# SCH_ESPHome-Aldes-T_One-V2.net
KiCad netlist of a schematic drawn in EasyEDA
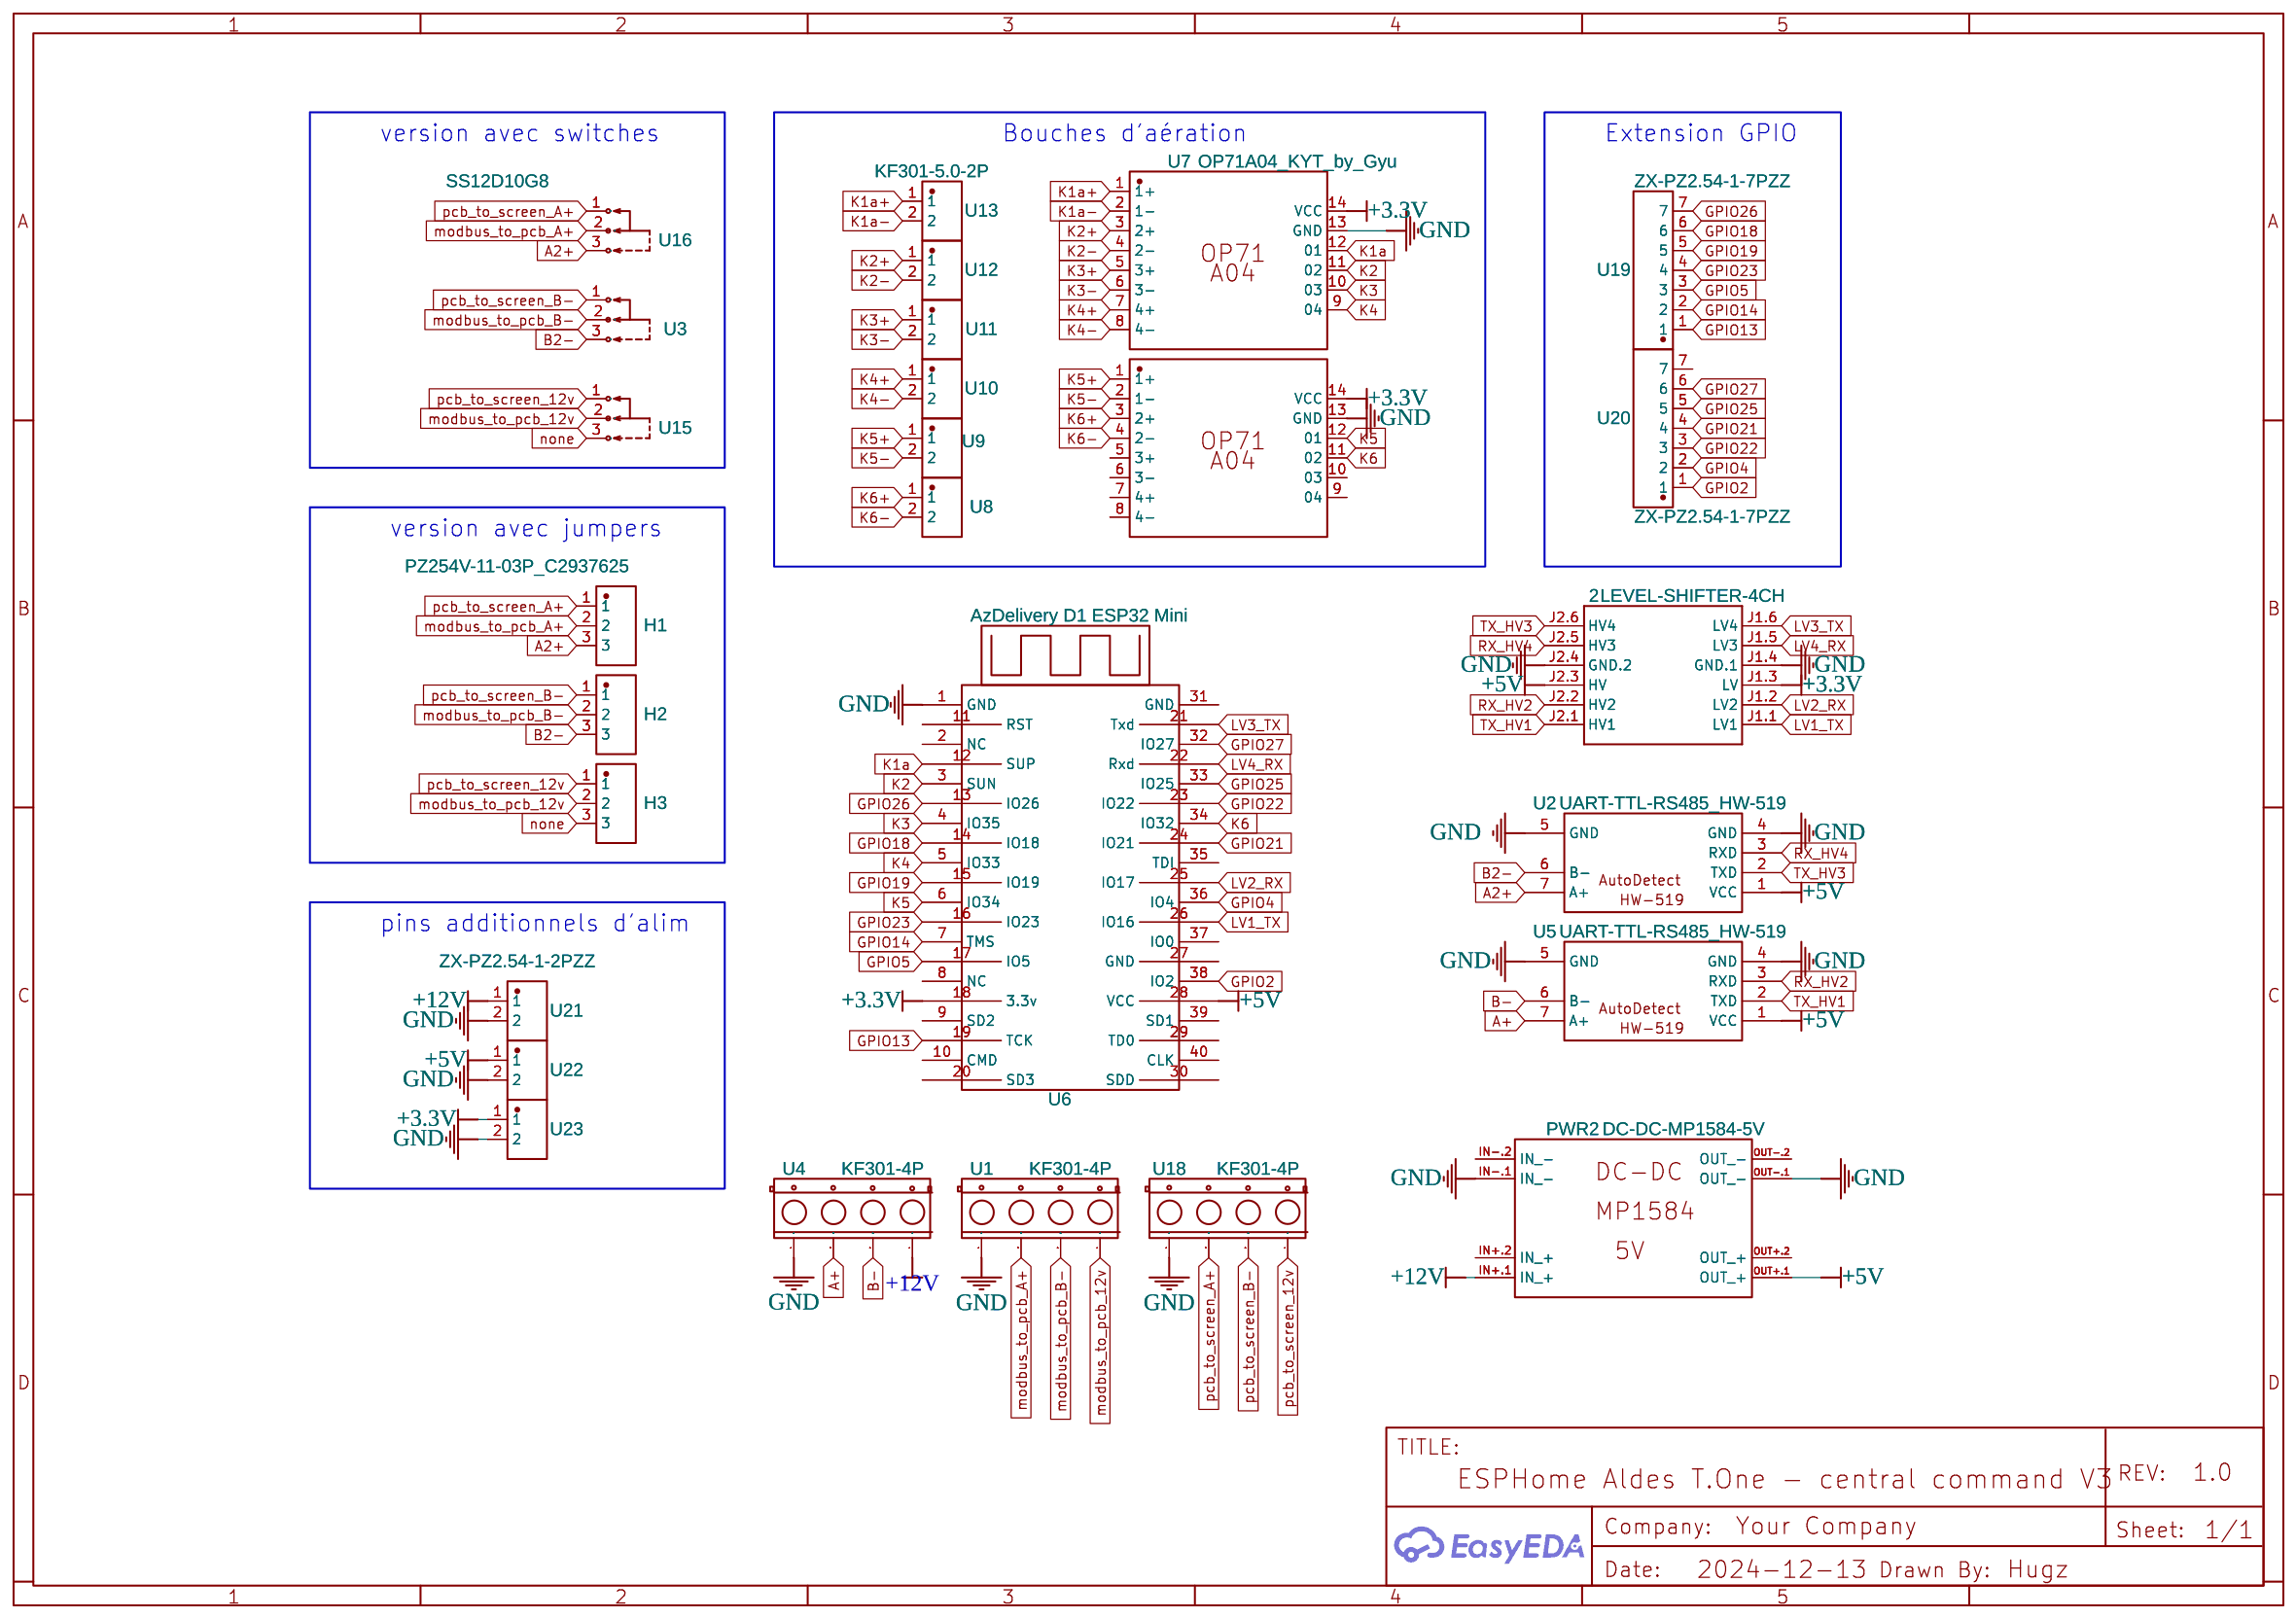
[diagram p0: schematic sheet]

(export (version "E")
  (design (tool "Eeschema 10.0.6"))
  (components
    (comp (ref "2") (value "LEVEL-SHIFTER-4CH") (libsource (lib "") (part "LEVEL-SHIFTER-4CH")))
    (comp (ref "H1")
      (value "PZ254V-11-03P_C2937625")
      (fields (field (name "Manufacturer Part") "PZ254V-11-03P") (field (name "Manufacturer") "XFCN(兴飞)"))
      (libsource (lib "") (part "PZ254V-11-03P_C2937625"))
    )
    (comp (ref "H2")
      (value "PZ254V-11-03P_C2937625")
      (fields (field (name "Manufacturer Part") "PZ254V-11-03P") (field (name "Manufacturer") "XFCN(兴飞)"))
      (libsource (lib "") (part "PZ254V-11-03P_C2937625"))
    )
    (comp (ref "H3")
      (value "PZ254V-11-03P_C2937625")
      (fields (field (name "Manufacturer Part") "PZ254V-11-03P") (field (name "Manufacturer") "XFCN(兴飞)"))
      (libsource (lib "") (part "PZ254V-11-03P_C2937625"))
    )
    (comp (ref "PWR2") (value "DC-DC-MP1584-5V") (libsource (lib "") (part "DC-DC-MP1584-5V")))
    (comp (ref "U1")
      (value "KF301-4P")
      (fields (field (name "Manufacturer Part") "KF301"))
      (libsource (lib "") (part "KF301-4P"))
    )
    (comp (ref "U2") (value "UART-TTL-RS485_HW-519") (libsource (lib "") (part "UART-TTL-RS485_HW-519")))
    (comp (ref "U3") (value "SS12D10G8") (libsource (lib "") (part "SS12D10G8")))
    (comp (ref "U4")
      (value "KF301-4P")
      (fields (field (name "Manufacturer Part") "KF301"))
      (libsource (lib "") (part "KF301-4P"))
    )
    (comp (ref "U5") (value "UART-TTL-RS485_HW-519") (libsource (lib "") (part "UART-TTL-RS485_HW-519")))
    (comp (ref "U6")
      (value "AzDelivery D1 ESP32 Mini")
      (fields (field (name "Manufacturer Part") "D1 Mini ESP32") (field (name "Manufacturer") "AzDelivery"))
      (libsource (lib "") (part "AzDelivery D1 ESP32 Mini"))
    )
    (comp (ref "U7") (value "OP71A04_KYT_by_Gyu") (libsource (lib "") (part "OP71A04_KYT_by_Gyu")))
    (comp (ref "U8")
      (value "KF301-5.0-2P")
      (fields (field (name "Manufacturer") "KEFA(科发)"))
      (libsource (lib "") (part "KF301-5.0-2P"))
    )
    (comp (ref "U9")
      (value "KF301-5.0-2P")
      (fields (field (name "Manufacturer") "KEFA(科发)"))
      (libsource (lib "") (part "KF301-5.0-2P"))
    )
    (comp (ref "U10")
      (value "KF301-5.0-2P")
      (fields (field (name "Manufacturer") "KEFA(科发)"))
      (libsource (lib "") (part "KF301-5.0-2P"))
    )
    (comp (ref "U11")
      (value "KF301-5.0-2P")
      (fields (field (name "Manufacturer") "KEFA(科发)"))
      (libsource (lib "") (part "KF301-5.0-2P"))
    )
    (comp (ref "U12")
      (value "KF301-5.0-2P")
      (fields (field (name "Manufacturer") "KEFA(科发)"))
      (libsource (lib "") (part "KF301-5.0-2P"))
    )
    (comp (ref "U13")
      (value "KF301-5.0-2P")
      (fields (field (name "Manufacturer") "KEFA(科发)"))
      (libsource (lib "") (part "KF301-5.0-2P"))
    )
    (comp (ref "U14") (value "OP71A04_KYT_by_Gyu") (libsource (lib "") (part "OP71A04_KYT_by_Gyu")))
    (comp (ref "U15") (value "SS12D10G8") (libsource (lib "") (part "SS12D10G8")))
    (comp (ref "U16") (value "SS12D10G8") (libsource (lib "") (part "SS12D10G8")))
    (comp (ref "U18")
      (value "KF301-4P")
      (fields (field (name "Manufacturer Part") "KF301"))
      (libsource (lib "") (part "KF301-4P"))
    )
    (comp (ref "U19")
      (value "ZX-PZ2.54-1-7PZZ")
      (fields (field (name "Manufacturer") "Megastar(兆星)"))
      (libsource (lib "") (part "ZX-PZ2.54-1-7PZZ"))
    )
    (comp (ref "U20")
      (value "ZX-PZ2.54-1-7PZZ")
      (fields (field (name "Manufacturer") "Megastar(兆星)"))
      (libsource (lib "") (part "ZX-PZ2.54-1-7PZZ"))
    )
    (comp (ref "U21")
      (value "ZX-PZ2.54-1-2PZZ")
      (fields (field (name "Manufacturer") "Megastar(兆星)"))
      (libsource (lib "") (part "ZX-PZ2.54-1-2PZZ"))
    )
    (comp (ref "U22")
      (value "ZX-PZ2.54-1-2PZZ")
      (fields (field (name "Manufacturer") "Megastar(兆星)"))
      (libsource (lib "") (part "ZX-PZ2.54-1-2PZZ"))
    )
    (comp (ref "U23")
      (value "ZX-PZ2.54-1-2PZZ")
      (fields (field (name "Manufacturer") "Megastar(兆星)"))
      (libsource (lib "") (part "ZX-PZ2.54-1-2PZZ"))
    )
  )
  (nets
    (net (code "1") (name "+3.3V") (class "Default")
      (node (ref "2") (pin "J1.3") (pinfunction "LV_J1.3") (pintype "bidirectional"))
      (node (ref "U14") (pin "14") (pinfunction "VCC_14") (pintype "unspecified"))
      (node (ref "U23") (pin "1") (pinfunction "1_1") (pintype "unspecified"))
      (node (ref "U6") (pin "18") (pinfunction "3.3v_18") (pintype "unspecified"))
      (node (ref "U7") (pin "14") (pinfunction "VCC_14") (pintype "unspecified"))
    )
    (net (code "2") (name "+5V") (class "Default")
      (node (ref "2") (pin "J2.3") (pinfunction "HV_J2.3") (pintype "bidirectional"))
      (node (ref "PWR2") (pin "OUT+.1") (pinfunction "OUT_+_OUT+.1") (pintype "unspecified"))
      (node (ref "U2") (pin "1") (pinfunction "VCC_1") (pintype "unspecified"))
      (node (ref "U22") (pin "1") (pinfunction "1_1") (pintype "unspecified"))
      (node (ref "U5") (pin "1") (pinfunction "VCC_1") (pintype "unspecified"))
      (node (ref "U6") (pin "28") (pinfunction "VCC_28") (pintype "unspecified"))
    )
    (net (code "3") (name "+12V") (class "Default")
      (node (ref "PWR2") (pin "IN+.1") (pinfunction "IN_+_IN+.1") (pintype "unspecified"))
      (node (ref "U21") (pin "1") (pinfunction "1_1") (pintype "unspecified"))
      (node (ref "U4") (pin "4") (pinfunction "4_4") (pintype "unspecified"))
    )
    (net (code "4") (name "A+") (class "Default")
      (node (ref "U4") (pin "2") (pinfunction "2_2") (pintype "unspecified"))
      (node (ref "U5") (pin "7") (pinfunction "A+_7") (pintype "unspecified"))
    )
    (net (code "5") (name "A2+") (class "Default")
      (node (ref "H1") (pin "3") (pinfunction "3_3") (pintype "unspecified"))
      (node (ref "U16") (pin "3") (pinfunction "3_3") (pintype "unspecified"))
      (node (ref "U2") (pin "7") (pinfunction "A+_7") (pintype "unspecified"))
    )
    (net (code "6") (name "B-") (class "Default")
      (node (ref "U4") (pin "3") (pinfunction "3_3") (pintype "unspecified"))
      (node (ref "U5") (pin "6") (pinfunction "B-_6") (pintype "unspecified"))
    )
    (net (code "7") (name "B2-") (class "Default")
      (node (ref "H2") (pin "3") (pinfunction "3_3") (pintype "unspecified"))
      (node (ref "U2") (pin "6") (pinfunction "B-_6") (pintype "unspecified"))
      (node (ref "U3") (pin "3") (pinfunction "3_3") (pintype "unspecified"))
    )
    (net (code "8") (name "GND") (class "Default")
      (node (ref "2") (pin "J1.4") (pinfunction "GND.1_J1.4") (pintype "bidirectional"))
      (node (ref "2") (pin "J2.4") (pinfunction "GND.2_J2.4") (pintype "bidirectional"))
      (node (ref "PWR2") (pin "IN-.1") (pinfunction "IN_-_IN-.1") (pintype "unspecified"))
      (node (ref "PWR2") (pin "OUT-.1") (pinfunction "OUT_-_OUT-.1") (pintype "unspecified"))
      (node (ref "U1") (pin "1") (pinfunction "1_1") (pintype "unspecified"))
      (node (ref "U14") (pin "13") (pinfunction "GND_13") (pintype "unspecified"))
      (node (ref "U18") (pin "1") (pinfunction "1_1") (pintype "unspecified"))
      (node (ref "U2") (pin "4") (pinfunction "GND_4") (pintype "unspecified"))
      (node (ref "U2") (pin "5") (pinfunction "GND_5") (pintype "unspecified"))
      (node (ref "U21") (pin "2") (pinfunction "2_2") (pintype "unspecified"))
      (node (ref "U22") (pin "2") (pinfunction "2_2") (pintype "unspecified"))
      (node (ref "U23") (pin "2") (pinfunction "2_2") (pintype "unspecified"))
      (node (ref "U4") (pin "1") (pinfunction "1_1") (pintype "unspecified"))
      (node (ref "U5") (pin "4") (pinfunction "GND_4") (pintype "unspecified"))
      (node (ref "U5") (pin "5") (pinfunction "GND_5") (pintype "unspecified"))
      (node (ref "U6") (pin "1") (pinfunction "GND_1") (pintype "unspecified"))
      (node (ref "U7") (pin "13") (pinfunction "GND_13") (pintype "unspecified"))
    )
    (net (code "9") (name "GPIO2") (class "Default")
      (node (ref "U20") (pin "1") (pinfunction "1_1") (pintype "unspecified"))
      (node (ref "U6") (pin "38") (pinfunction "IO2_38") (pintype "unspecified"))
    )
    (net (code "10") (name "GPIO4") (class "Default")
      (node (ref "U20") (pin "2") (pinfunction "2_2") (pintype "unspecified"))
      (node (ref "U6") (pin "36") (pinfunction "IO4_36") (pintype "unspecified"))
    )
    (net (code "11") (name "GPIO5") (class "Default")
      (node (ref "U19") (pin "3") (pinfunction "3_3") (pintype "unspecified"))
      (node (ref "U6") (pin "17") (pinfunction "IO5_17") (pintype "unspecified"))
    )
    (net (code "12") (name "GPIO13") (class "Default")
      (node (ref "U19") (pin "1") (pinfunction "1_1") (pintype "unspecified"))
      (node (ref "U6") (pin "19") (pinfunction "TCK_19") (pintype "unspecified"))
    )
    (net (code "13") (name "GPIO14") (class "Default")
      (node (ref "U19") (pin "2") (pinfunction "2_2") (pintype "unspecified"))
      (node (ref "U6") (pin "7") (pinfunction "TMS_7") (pintype "unspecified"))
    )
    (net (code "14") (name "GPIO18") (class "Default")
      (node (ref "U19") (pin "6") (pinfunction "6_6") (pintype "unspecified"))
      (node (ref "U6") (pin "14") (pinfunction "IO18_14") (pintype "unspecified"))
    )
    (net (code "15") (name "GPIO19") (class "Default")
      (node (ref "U19") (pin "5") (pinfunction "5_5") (pintype "unspecified"))
      (node (ref "U6") (pin "15") (pinfunction "IO19_15") (pintype "unspecified"))
    )
    (net (code "16") (name "GPIO21") (class "Default")
      (node (ref "U20") (pin "4") (pinfunction "4_4") (pintype "unspecified"))
      (node (ref "U6") (pin "24") (pinfunction "IO21_24") (pintype "unspecified"))
    )
    (net (code "17") (name "GPIO22") (class "Default")
      (node (ref "U20") (pin "3") (pinfunction "3_3") (pintype "unspecified"))
      (node (ref "U6") (pin "23") (pinfunction "IO22_23") (pintype "unspecified"))
    )
    (net (code "18") (name "GPIO23") (class "Default")
      (node (ref "U19") (pin "4") (pinfunction "4_4") (pintype "unspecified"))
      (node (ref "U6") (pin "16") (pinfunction "IO23_16") (pintype "unspecified"))
    )
    (net (code "19") (name "GPIO25") (class "Default")
      (node (ref "U20") (pin "5") (pinfunction "5_5") (pintype "unspecified"))
      (node (ref "U6") (pin "33") (pinfunction "IO25_33") (pintype "unspecified"))
    )
    (net (code "20") (name "GPIO26") (class "Default")
      (node (ref "U19") (pin "7") (pinfunction "7_7") (pintype "unspecified"))
      (node (ref "U6") (pin "13") (pinfunction "IO26_13") (pintype "unspecified"))
    )
    (net (code "21") (name "GPIO27") (class "Default")
      (node (ref "U20") (pin "6") (pinfunction "6_6") (pintype "unspecified"))
      (node (ref "U6") (pin "32") (pinfunction "IO27_32") (pintype "unspecified"))
    )
    (net (code "22") (name "K1a") (class "Default")
      (node (ref "U6") (pin "12") (pinfunction "SUP_12") (pintype "unspecified"))
      (node (ref "U7") (pin "12") (pinfunction "01_12") (pintype "unspecified"))
    )
    (net (code "23") (name "K1a+") (class "Default")
      (node (ref "U13") (pin "1") (pinfunction "1_1") (pintype "unspecified"))
      (node (ref "U7") (pin "1") (pinfunction "1+_1") (pintype "unspecified"))
    )
    (net (code "24") (name "K1a-") (class "Default")
      (node (ref "U13") (pin "2") (pinfunction "2_2") (pintype "unspecified"))
      (node (ref "U7") (pin "2") (pinfunction "1-_2") (pintype "unspecified"))
    )
    (net (code "25") (name "K2") (class "Default")
      (node (ref "U6") (pin "3") (pinfunction "SUN_3") (pintype "unspecified"))
      (node (ref "U7") (pin "11") (pinfunction "02_11") (pintype "unspecified"))
    )
    (net (code "26") (name "K2+") (class "Default")
      (node (ref "U12") (pin "1") (pinfunction "1_1") (pintype "unspecified"))
      (node (ref "U7") (pin "3") (pinfunction "2+_3") (pintype "unspecified"))
    )
    (net (code "27") (name "K2-") (class "Default")
      (node (ref "U12") (pin "2") (pinfunction "2_2") (pintype "unspecified"))
      (node (ref "U7") (pin "4") (pinfunction "2-_4") (pintype "unspecified"))
    )
    (net (code "28") (name "K3") (class "Default")
      (node (ref "U6") (pin "4") (pinfunction "IO35_4") (pintype "unspecified"))
      (node (ref "U7") (pin "10") (pinfunction "03_10") (pintype "unspecified"))
    )
    (net (code "29") (name "K3+") (class "Default")
      (node (ref "U11") (pin "1") (pinfunction "1_1") (pintype "unspecified"))
      (node (ref "U7") (pin "5") (pinfunction "3+_5") (pintype "unspecified"))
    )
    (net (code "30") (name "K3-") (class "Default")
      (node (ref "U11") (pin "2") (pinfunction "2_2") (pintype "unspecified"))
      (node (ref "U7") (pin "6") (pinfunction "3-_6") (pintype "unspecified"))
    )
    (net (code "31") (name "K4") (class "Default")
      (node (ref "U6") (pin "5") (pinfunction "IO33_5") (pintype "unspecified"))
      (node (ref "U7") (pin "9") (pinfunction "04_9") (pintype "unspecified"))
    )
    (net (code "32") (name "K4+") (class "Default")
      (node (ref "U10") (pin "1") (pinfunction "1_1") (pintype "unspecified"))
      (node (ref "U7") (pin "7") (pinfunction "4+_7") (pintype "unspecified"))
    )
    (net (code "33") (name "K4-") (class "Default")
      (node (ref "U10") (pin "2") (pinfunction "2_2") (pintype "unspecified"))
      (node (ref "U7") (pin "8") (pinfunction "4-_8") (pintype "unspecified"))
    )
    (net (code "34") (name "K5") (class "Default")
      (node (ref "U14") (pin "12") (pinfunction "01_12") (pintype "unspecified"))
      (node (ref "U6") (pin "6") (pinfunction "IO34_6") (pintype "unspecified"))
    )
    (net (code "35") (name "K5+") (class "Default")
      (node (ref "U14") (pin "1") (pinfunction "1+_1") (pintype "unspecified"))
      (node (ref "U9") (pin "1") (pinfunction "1_1") (pintype "unspecified"))
    )
    (net (code "36") (name "K5-") (class "Default")
      (node (ref "U14") (pin "2") (pinfunction "1-_2") (pintype "unspecified"))
      (node (ref "U9") (pin "2") (pinfunction "2_2") (pintype "unspecified"))
    )
    (net (code "37") (name "K6") (class "Default")
      (node (ref "U14") (pin "11") (pinfunction "02_11") (pintype "unspecified"))
      (node (ref "U6") (pin "34") (pinfunction "IO32_34") (pintype "unspecified"))
    )
    (net (code "38") (name "K6+") (class "Default")
      (node (ref "U14") (pin "3") (pinfunction "2+_3") (pintype "unspecified"))
      (node (ref "U8") (pin "1") (pinfunction "1_1") (pintype "unspecified"))
    )
    (net (code "39") (name "K6-") (class "Default")
      (node (ref "U14") (pin "4") (pinfunction "2-_4") (pintype "unspecified"))
      (node (ref "U8") (pin "2") (pinfunction "2_2") (pintype "unspecified"))
    )
    (net (code "40") (name "LV1_TX") (class "Default")
      (node (ref "2") (pin "J1.1") (pinfunction "LV1_J1.1") (pintype "bidirectional"))
      (node (ref "U6") (pin "26") (pinfunction "IO16_26") (pintype "unspecified"))
    )
    (net (code "41") (name "LV2_RX") (class "Default")
      (node (ref "2") (pin "J1.2") (pinfunction "LV2_J1.2") (pintype "bidirectional"))
      (node (ref "U6") (pin "25") (pinfunction "IO17_25") (pintype "unspecified"))
    )
    (net (code "42") (name "LV3_TX") (class "Default")
      (node (ref "2") (pin "J1.6") (pinfunction "LV4_J1.6") (pintype "bidirectional"))
      (node (ref "U6") (pin "21") (pinfunction "Txd_21") (pintype "unspecified"))
    )
    (net (code "43") (name "LV4_RX") (class "Default")
      (node (ref "2") (pin "J1.5") (pinfunction "LV3_J1.5") (pintype "bidirectional"))
      (node (ref "U6") (pin "22") (pinfunction "Rxd_22") (pintype "unspecified"))
    )
    (net (code "44") (name "RX_HV2") (class "Default")
      (node (ref "2") (pin "J2.2") (pinfunction "HV2_J2.2") (pintype "bidirectional"))
      (node (ref "U5") (pin "3") (pinfunction "RXD_3") (pintype "unspecified"))
    )
    (net (code "45") (name "RX_HV4") (class "Default")
      (node (ref "2") (pin "J2.5") (pinfunction "HV3_J2.5") (pintype "bidirectional"))
      (node (ref "U2") (pin "3") (pinfunction "RXD_3") (pintype "unspecified"))
    )
    (net (code "46") (name "TX_HV1") (class "Default")
      (node (ref "2") (pin "J2.1") (pinfunction "HV1_J2.1") (pintype "bidirectional"))
      (node (ref "U5") (pin "2") (pinfunction "TXD_2") (pintype "unspecified"))
    )
    (net (code "47") (name "TX_HV3") (class "Default")
      (node (ref "2") (pin "J2.6") (pinfunction "HV4_J2.6") (pintype "bidirectional"))
      (node (ref "U2") (pin "2") (pinfunction "TXD_2") (pintype "unspecified"))
    )
    (net (code "48") (name "modbus_to_pcb_12v") (class "Default")
      (node (ref "H3") (pin "2") (pinfunction "2_2") (pintype "unspecified"))
      (node (ref "U1") (pin "4") (pinfunction "4_4") (pintype "unspecified"))
      (node (ref "U15") (pin "2") (pinfunction "2_2") (pintype "unspecified"))
    )
    (net (code "49") (name "modbus_to_pcb_A+") (class "Default")
      (node (ref "H1") (pin "2") (pinfunction "2_2") (pintype "unspecified"))
      (node (ref "U1") (pin "2") (pinfunction "2_2") (pintype "unspecified"))
      (node (ref "U16") (pin "2") (pinfunction "2_2") (pintype "unspecified"))
    )
    (net (code "50") (name "modbus_to_pcb_B-") (class "Default")
      (node (ref "H2") (pin "2") (pinfunction "2_2") (pintype "unspecified"))
      (node (ref "U1") (pin "3") (pinfunction "3_3") (pintype "unspecified"))
      (node (ref "U3") (pin "2") (pinfunction "2_2") (pintype "unspecified"))
    )
    (net (code "51") (name "none") (class "Default")
      (node (ref "H3") (pin "3") (pinfunction "3_3") (pintype "unspecified"))
      (node (ref "U15") (pin "3") (pinfunction "3_3") (pintype "unspecified"))
    )
    (net (code "52") (name "pcb_to_screen_12v") (class "Default")
      (node (ref "H3") (pin "1") (pinfunction "1_1") (pintype "unspecified"))
      (node (ref "U15") (pin "1") (pinfunction "1_1") (pintype "unspecified"))
      (node (ref "U18") (pin "4") (pinfunction "4_4") (pintype "unspecified"))
    )
    (net (code "53") (name "pcb_to_screen_A+") (class "Default")
      (node (ref "H1") (pin "1") (pinfunction "1_1") (pintype "unspecified"))
      (node (ref "U16") (pin "1") (pinfunction "1_1") (pintype "unspecified"))
      (node (ref "U18") (pin "2") (pinfunction "2_2") (pintype "unspecified"))
    )
    (net (code "54") (name "pcb_to_screen_B-") (class "Default")
      (node (ref "H2") (pin "1") (pinfunction "1_1") (pintype "unspecified"))
      (node (ref "U18") (pin "3") (pinfunction "3_3") (pintype "unspecified"))
      (node (ref "U3") (pin "1") (pinfunction "1_1") (pintype "unspecified"))
    )
    (net (code "55") (name "unconnected-(PWR2-IN_+-PadIN+.2)") (class "Default")
      (node (ref "PWR2") (pin "IN+.2") (pinfunction "IN_+_IN+.2") (pintype "unspecified"))
    )
    (net (code "56") (name "unconnected-(PWR2-IN_--PadIN-.2)") (class "Default")
      (node (ref "PWR2") (pin "IN-.2") (pinfunction "IN_-_IN-.2") (pintype "unspecified"))
    )
    (net (code "57") (name "unconnected-(PWR2-OUT_+-PadOUT+.2)") (class "Default")
      (node (ref "PWR2") (pin "OUT+.2") (pinfunction "OUT_+_OUT+.2") (pintype "unspecified"))
    )
    (net (code "58") (name "unconnected-(PWR2-OUT_--PadOUT-.2)") (class "Default")
      (node (ref "PWR2") (pin "OUT-.2") (pinfunction "OUT_-_OUT-.2") (pintype "unspecified"))
    )
    (net (code "59") (name "unconnected-(U6-CLK-Pad40)") (class "Default")
      (node (ref "U6") (pin "40") (pinfunction "CLK_40") (pintype "unspecified"))
    )
    (net (code "60") (name "unconnected-(U6-CMD-Pad10)") (class "Default")
      (node (ref "U6") (pin "10") (pinfunction "CMD_10") (pintype "unspecified"))
    )
    (net (code "61") (name "unconnected-(U6-GND-Pad27)") (class "Default")
      (node (ref "U6") (pin "27") (pinfunction "GND_27") (pintype "unspecified"))
    )
    (net (code "62") (name "unconnected-(U6-GND-Pad31)") (class "Default")
      (node (ref "U6") (pin "31") (pinfunction "GND_31") (pintype "unspecified"))
    )
    (net (code "63") (name "unconnected-(U6-IO0-Pad37)") (class "Default")
      (node (ref "U6") (pin "37") (pinfunction "IO0_37") (pintype "unspecified"))
    )
    (net (code "64") (name "unconnected-(U6-NC-Pad2)") (class "Default")
      (node (ref "U6") (pin "2") (pinfunction "NC_2") (pintype "unspecified"))
    )
    (net (code "65") (name "unconnected-(U6-NC-Pad8)") (class "Default")
      (node (ref "U6") (pin "8") (pinfunction "NC_8") (pintype "unspecified"))
    )
    (net (code "66") (name "unconnected-(U6-RST-Pad11)") (class "Default")
      (node (ref "U6") (pin "11") (pinfunction "RST_11") (pintype "unspecified"))
    )
    (net (code "67") (name "unconnected-(U6-SD1-Pad39)") (class "Default")
      (node (ref "U6") (pin "39") (pinfunction "SD1_39") (pintype "unspecified"))
    )
    (net (code "68") (name "unconnected-(U6-SD2-Pad9)") (class "Default")
      (node (ref "U6") (pin "9") (pinfunction "SD2_9") (pintype "unspecified"))
    )
    (net (code "69") (name "unconnected-(U6-SD3-Pad20)") (class "Default")
      (node (ref "U6") (pin "20") (pinfunction "SD3_20") (pintype "unspecified"))
    )
    (net (code "70") (name "unconnected-(U6-SDD-Pad30)") (class "Default")
      (node (ref "U6") (pin "30") (pinfunction "SDD_30") (pintype "unspecified"))
    )
    (net (code "71") (name "unconnected-(U6-TD0-Pad29)") (class "Default")
      (node (ref "U6") (pin "29") (pinfunction "TD0_29") (pintype "unspecified"))
    )
    (net (code "72") (name "unconnected-(U6-TDI-Pad35)") (class "Default")
      (node (ref "U6") (pin "35") (pinfunction "TDI_35") (pintype "unspecified"))
    )
    (net (code "73") (name "unconnected-(U14-3+-Pad5)") (class "Default")
      (node (ref "U14") (pin "5") (pinfunction "3+_5") (pintype "unspecified"))
    )
    (net (code "74") (name "unconnected-(U14-3--Pad6)") (class "Default")
      (node (ref "U14") (pin "6") (pinfunction "3-_6") (pintype "unspecified"))
    )
    (net (code "75") (name "unconnected-(U14-03-Pad10)") (class "Default")
      (node (ref "U14") (pin "10") (pinfunction "03_10") (pintype "unspecified"))
    )
    (net (code "76") (name "unconnected-(U14-4+-Pad7)") (class "Default")
      (node (ref "U14") (pin "7") (pinfunction "4+_7") (pintype "unspecified"))
    )
    (net (code "77") (name "unconnected-(U14-4--Pad8)") (class "Default")
      (node (ref "U14") (pin "8") (pinfunction "4-_8") (pintype "unspecified"))
    )
    (net (code "78") (name "unconnected-(U14-04-Pad9)") (class "Default")
      (node (ref "U14") (pin "9") (pinfunction "04_9") (pintype "unspecified"))
    )
    (net (code "79") (name "unconnected-(U20-Pad7)") (class "Default")
      (node (ref "U20") (pin "7") (pinfunction "7_7") (pintype "unspecified"))
    )
  )
)
